# Integrators.net
KiCad netlist of a schematic drawn in Altium Designer
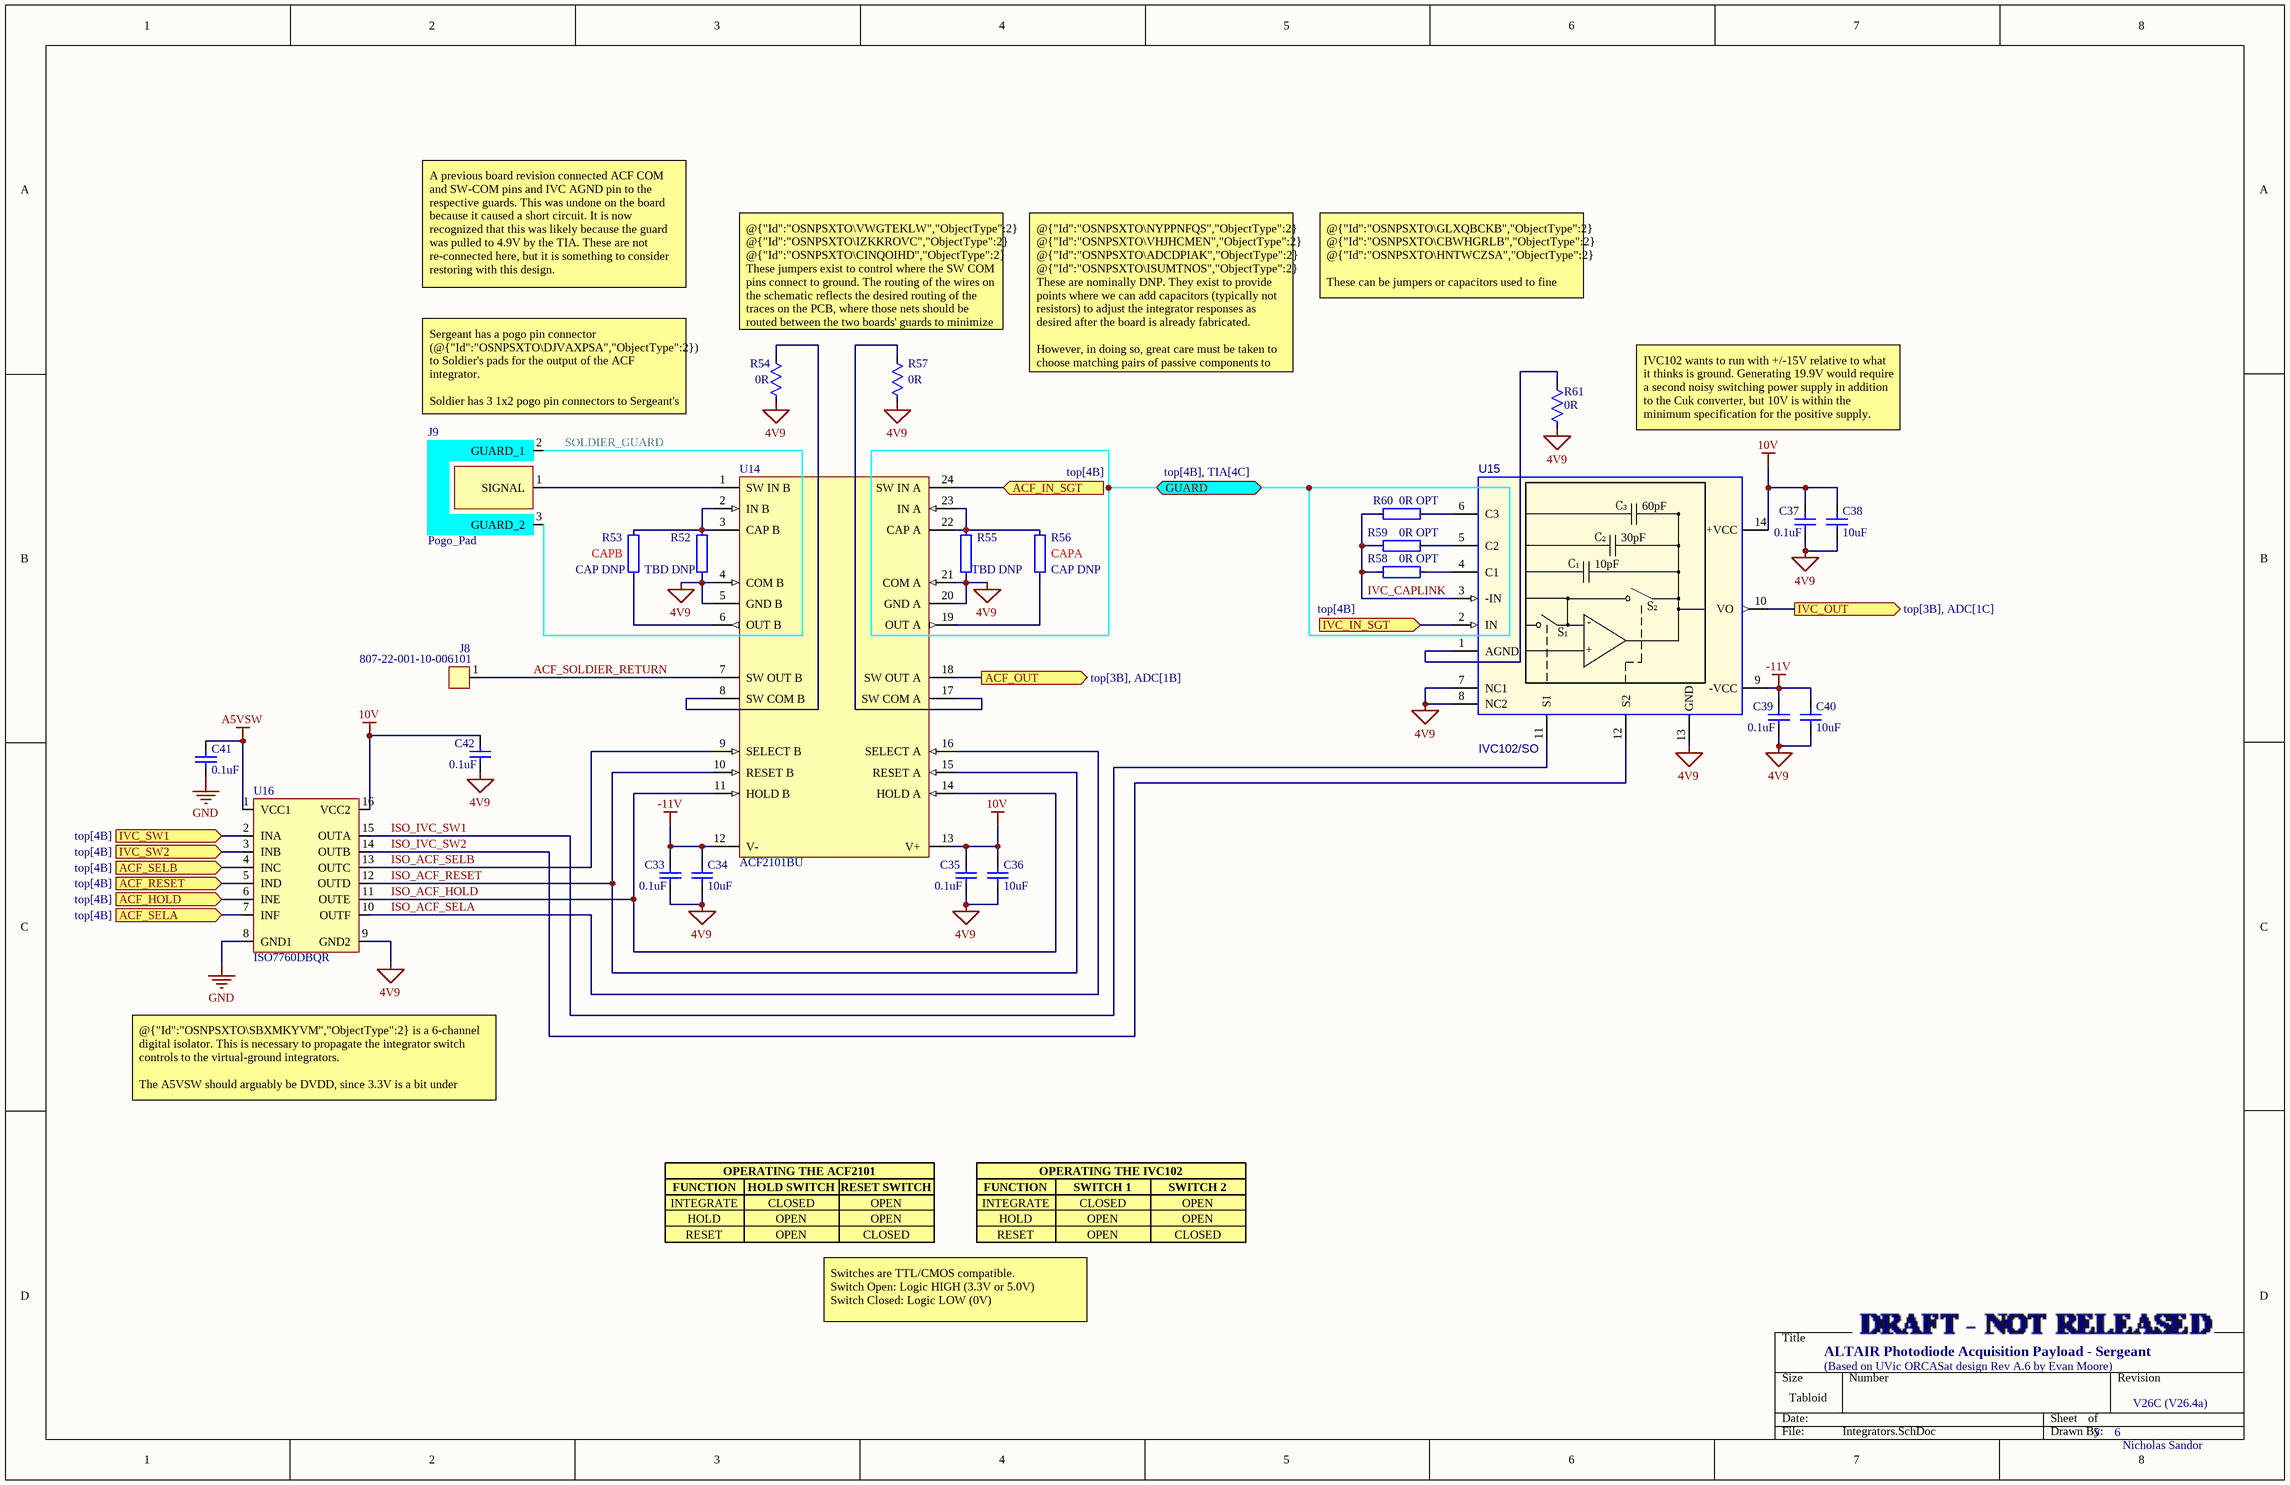
[diagram p0: Integrators.SchDoc]

(export (version "E")
  (design (tool "Eeschema 10.0.6"))
  (components
    (comp (ref "C33")
      (value "0.1uF")
      (footprint "CAP 0603 NON-IPC KEMET X7R")
      (description "Kemet C0603C104K5RACAUTO - Cap Ceramic 0.1uF 50V X7R 10% 0603 125C Paper T/R")
      (fields (field (name "MF") "Kemet") (field (name "MP") "C0603C104K5RACAUTO"))
      (libsource (lib "ALTAIR_PD_Capacitors") (part "CAP"))
    )
    (comp (ref "C34")
      (value "10uF")
      (footprint "CAP 0805 IPC MID DENSITY")
      (description "Murata GRM21BR61E106KA73L - Cap Ceramic 10uF 10% 25V X5R 0805")
      (fields (field (name "MF") "Murata") (field (name "MP") "GRM21BR61E106KA73L"))
      (libsource (lib "ALTAIR_PD_Capacitors") (part "CAP"))
    )
    (comp (ref "C35")
      (value "0.1uF")
      (footprint "CAP 0603 NON-IPC KEMET X7R")
      (description "Kemet C0603C104K5RACAUTO - Cap Ceramic 0.1uF 50V X7R 10% 0603 125C Paper T/R")
      (fields (field (name "MF") "Kemet") (field (name "MP") "C0603C104K5RACAUTO"))
      (libsource (lib "ALTAIR_PD_Capacitors") (part "CAP"))
    )
    (comp (ref "C36")
      (value "10uF")
      (footprint "CAP 0805 IPC MID DENSITY")
      (description "Murata GRM21BR61E106KA73L - Cap Ceramic 10uF 10% 25V X5R 0805")
      (fields (field (name "MF") "Murata") (field (name "MP") "GRM21BR61E106KA73L"))
      (libsource (lib "ALTAIR_PD_Capacitors") (part "CAP"))
    )
    (comp (ref "C37")
      (value "0.1uF")
      (footprint "CAP 0603 NON-IPC KEMET X7R")
      (description "Kemet C0603C104K5RACAUTO - Cap Ceramic 0.1uF 50V X7R 10% 0603 125C Paper T/R")
      (fields (field (name "MF") "Kemet") (field (name "MP") "C0603C104K5RACAUTO"))
      (libsource (lib "ALTAIR_PD_Capacitors") (part "CAP"))
    )
    (comp (ref "C38")
      (value "10uF")
      (footprint "CAP 0805 IPC MID DENSITY")
      (description "Murata GRM21BR61E106KA73L - Cap Ceramic 10uF 10% 25V X5R 0805")
      (fields (field (name "MF") "Murata") (field (name "MP") "GRM21BR61E106KA73L"))
      (libsource (lib "ALTAIR_PD_Capacitors") (part "CAP"))
    )
    (comp (ref "C39")
      (value "0.1uF")
      (footprint "CAP 0603 NON-IPC KEMET X7R")
      (description "Kemet C0603C104K5RACAUTO - Cap Ceramic 0.1uF 50V X7R 10% 0603 125C Paper T/R")
      (fields (field (name "MF") "Kemet") (field (name "MP") "C0603C104K5RACAUTO"))
      (libsource (lib "ALTAIR_PD_Capacitors") (part "CAP"))
    )
    (comp (ref "C40")
      (value "10uF")
      (footprint "CAP 0805 IPC MID DENSITY")
      (description "Murata GRM21BR61E106KA73L - Cap Ceramic 10uF 10% 25V X5R 0805")
      (fields (field (name "MF") "Murata") (field (name "MP") "GRM21BR61E106KA73L"))
      (libsource (lib "ALTAIR_PD_Capacitors") (part "CAP"))
    )
    (comp (ref "C41")
      (value "0.1uF")
      (footprint "CAP 0603 IPC MID DENSITY")
      (description "Kemet C0603C104K5RACAUTO - Cap Ceramic 0.1uF 50V X7R 10% 0603 125C Paper T/R")
      (fields (field (name "MF") "Kemet") (field (name "MP") "C0603C104K5RACAUTO"))
      (libsource (lib "ALTAIR_PD_Capacitors") (part "CAP"))
    )
    (comp (ref "C42")
      (value "0.1uF")
      (footprint "CAP 0603 IPC MID DENSITY")
      (description "Kemet C0603C104K5RACAUTO - Cap Ceramic 0.1uF 50V X7R 10% 0603 125C Paper T/R")
      (fields (field (name "MF") "Kemet") (field (name "MP") "C0603C104K5RACAUTO"))
      (libsource (lib "ALTAIR_PD_Capacitors") (part "CAP"))
    )
    (comp (ref "J8")
      (value "807-22-001-10-006101")
      (footprint "POGO PIN 807-22-001-10-006101")
      (description "Mill-Max Individual Insulated Pin 5.99mm Initial Height")
      (fields (field (name "MF") "Mill-Max"))
      (libsource (lib "ALTAIR_PD_Pogo") (part "807-22-001-10-006101"))
    )
    (comp (ref "J9")
      (value "Pogo_Pad")
      (footprint "POGO PAD SERGEANT")
      (description "Pad for Pogo Pins with Guard")
      (libsource (lib "ALTAIR_PD_Pogo") (part "Pogo_Pad"))
    )
    (comp (ref "R52")
      (value "TBD DNP")
      (footprint "RES 0402 IPC LOW DENSITY")
      (description "Yageo RC0402JR-070RL - Res 0 Ohms 1/16W SMD 0402")
      (fields (field (name "MF") "YAGEO") (field (name "MP") "RC0402JR-070RL"))
      (libsource (lib "ALTAIR_PD_Resistors") (part "IMPEDANCE"))
    )
    (comp (ref "R53")
      (value "CAP DNP")
      (footprint "RES 0402 IPC LOW DENSITY")
      (description "Yageo RC0402JR-070RL - Res 0 Ohms 1/16W SMD 0402")
      (fields (field (name "MF") "YAGEO") (field (name "MP") "RC0402JR-070RL"))
      (libsource (lib "ALTAIR_PD_Resistors") (part "IMPEDANCE"))
    )
    (comp (ref "R54")
      (value "0R")
      (footprint "RES 0402 IPC MID DENSITY")
      (description "Yageo RC0402JR-070RL - Res 0 Ohms 1/16W SMD 0402")
      (fields (field (name "MF") "YAGEO") (field (name "MP") "RC0402JR-070RL"))
      (libsource (lib "ALTAIR_PD_Resistors") (part "RES"))
    )
    (comp (ref "R55")
      (value "TBD DNP")
      (footprint "RES 0402 IPC LOW DENSITY")
      (description "Yageo RC0402JR-070RL - Res 0 Ohms 1/16W SMD 0402")
      (fields (field (name "MF") "YAGEO") (field (name "MP") "RC0402JR-070RL"))
      (libsource (lib "ALTAIR_PD_Resistors") (part "IMPEDANCE"))
    )
    (comp (ref "R56")
      (value "CAP DNP")
      (footprint "RES 0402 IPC LOW DENSITY")
      (description "Yageo RC0402JR-070RL - Res 0 Ohms 1/16W SMD 0402")
      (fields (field (name "MF") "YAGEO") (field (name "MP") "RC0402JR-070RL"))
      (libsource (lib "ALTAIR_PD_Resistors") (part "IMPEDANCE"))
    )
    (comp (ref "R57")
      (value "0R")
      (footprint "RES 0402 IPC MID DENSITY")
      (description "Yageo RC0402JR-070RL - Res 0 Ohms 1/16W SMD 0402")
      (fields (field (name "MF") "YAGEO") (field (name "MP") "RC0402JR-070RL"))
      (libsource (lib "ALTAIR_PD_Resistors") (part "RES"))
    )
    (comp (ref "R58")
      (value "0R OPT")
      (footprint "RES 0402 IPC LOW DENSITY")
      (description "Yageo RC0402JR-070RL - Res 0 Ohms 1/16W SMD 0402")
      (fields (field (name "MF") "YAGEO") (field (name "MP") "RC0402JR-070RL"))
      (libsource (lib "ALTAIR_PD_Resistors") (part "IMPEDANCE"))
    )
    (comp (ref "R59")
      (value "0R OPT")
      (footprint "RES 0402 IPC LOW DENSITY")
      (description "Yageo RC0402JR-070RL - Res 0 Ohms 1/16W SMD 0402")
      (fields (field (name "MF") "YAGEO") (field (name "MP") "RC0402JR-070RL"))
      (libsource (lib "ALTAIR_PD_Resistors") (part "IMPEDANCE"))
    )
    (comp (ref "R60")
      (value "0R OPT")
      (footprint "RES 0402 IPC LOW DENSITY")
      (description "Yageo RC0402JR-070RL - Res 0 Ohms 1/16W SMD 0402")
      (fields (field (name "MF") "YAGEO") (field (name "MP") "RC0402JR-070RL"))
      (libsource (lib "ALTAIR_PD_Resistors") (part "IMPEDANCE"))
    )
    (comp (ref "R61")
      (value "0R")
      (footprint "RES 0402 IPC MID DENSITY")
      (description "Yageo RC0402JR-070RL - Res 0 Ohms 1/16W SMD 0402")
      (fields (field (name "MF") "YAGEO") (field (name "MP") "RC0402JR-070RL"))
      (libsource (lib "ALTAIR_PD_Resistors") (part "RES"))
    )
    (comp (ref "U14")
      (value "ACF2101BU")
      (footprint "ALTAIR_PD_SOIC:24-SOIC 7.6MM WIDE LOW DENSITY")
      (fields (field (name "MF") "Texas Instruments"))
      (libsource (lib "ALTAIR_PD_Amplifiers") (part "ACF2101BU"))
    )
    (comp (ref "U15")
      (value "IVC102/SO")
      (footprint "14-SOIC 4MM WIDE LOW DENSITY")
      (description "Precision Switched Integrator Transimpedance Amplifier")
      (fields (field (name "MF") "Texas Instruments") (field (name "MP") "IVC102U"))
      (libsource (lib "ALTAIR_PD_Amplifiers") (part "IVC102/SO_5"))
    )
    (comp (ref "U16")
      (value "ISO7760DBQR")
      (footprint "16-SSOP 0.635MM PITCH 5.4MM WIDTH NON-IPC TI")
      (description "Digital Isolator 6-Channel 6/0 Inputs 16SSOP")
      (fields (field (name "MF") "Texas Instruments"))
      (libsource (lib "ALTAIR_PD_DigitalLogic") (part "ISO7760DBQR"))
    )
  )
  (nets
    (net (code "1") (name "-11V") (class "Default")
      (node (ref "C33") (pin "2") (pinfunction "2_2") (pintype "passive"))
      (node (ref "C34") (pin "2") (pinfunction "2_2") (pintype "passive"))
      (node (ref "C39") (pin "2") (pinfunction "2_2") (pintype "passive"))
      (node (ref "C40") (pin "2") (pinfunction "2_2") (pintype "passive"))
      (node (ref "U14") (pin "12") (pinfunction "V-_12") (pintype "power_in"))
      (node (ref "U15") (pin "9") (pinfunction "-VCC_9") (pintype "power_in"))
    )
    (net (code "2") (name "/ACF_HOLD") (class "Default")
      (node (ref "U16") (pin "6") (pinfunction "INE_6") (pintype "passive"))
    )
    (net (code "3") (name "/ACF_IN_SGT") (class "Default")
      (node (ref "U14") (pin "24") (pinfunction "SW_IN_A_24") (pintype "passive"))
    )
    (net (code "4") (name "/ACF_OUT") (class "Default")
      (node (ref "U14") (pin "18") (pinfunction "SW_OUT_A_18") (pintype "passive"))
    )
    (net (code "5") (name "/ACF_RESET") (class "Default")
      (node (ref "U16") (pin "5") (pinfunction "IND_5") (pintype "passive"))
    )
    (net (code "6") (name "/ACF_SELA") (class "Default")
      (node (ref "U16") (pin "7") (pinfunction "INF_7") (pintype "passive"))
    )
    (net (code "7") (name "/ACF_SELB") (class "Default")
      (node (ref "U16") (pin "4") (pinfunction "INC_4") (pintype "passive"))
    )
    (net (code "8") (name "/ACF_SOLDIER_RETURN") (class "Default")
      (node (ref "J8") (pin "1") (pinfunction "1_1") (pintype "passive"))
      (node (ref "U14") (pin "7") (pinfunction "SW_OUT_B_7") (pintype "passive"))
    )
    (net (code "10") (name "/ISO_ACF_HOLD") (class "Default")
      (node (ref "U14") (pin "11") (pinfunction "HOLD_B_11") (pintype "input"))
      (node (ref "U14") (pin "14") (pinfunction "HOLD_A_14") (pintype "input"))
      (node (ref "U16") (pin "11") (pinfunction "OUTE_11") (pintype "passive"))
    )
    (net (code "11") (name "/ISO_ACF_RESET") (class "Default")
      (node (ref "U14") (pin "10") (pinfunction "RESET_B_10") (pintype "input"))
      (node (ref "U14") (pin "15") (pinfunction "RESET_A_15") (pintype "input"))
      (node (ref "U16") (pin "12") (pinfunction "OUTD_12") (pintype "passive"))
    )
    (net (code "12") (name "/ISO_ACF_SELA") (class "Default")
      (node (ref "U14") (pin "16") (pinfunction "SELECT_A_16") (pintype "input"))
      (node (ref "U16") (pin "10") (pinfunction "OUTF_10") (pintype "passive"))
    )
    (net (code "13") (name "/ISO_ACF_SELB") (class "Default")
      (node (ref "U14") (pin "9") (pinfunction "SELECT_B_9") (pintype "input"))
      (node (ref "U16") (pin "13") (pinfunction "OUTC_13") (pintype "passive"))
    )
    (net (code "14") (name "/ISO_IVC_SW1") (class "Default")
      (node (ref "U15") (pin "11") (pinfunction "S1_11") (pintype "passive"))
      (node (ref "U16") (pin "15") (pinfunction "OUTA_15") (pintype "passive"))
    )
    (net (code "15") (name "/ISO_IVC_SW2") (class "Default")
      (node (ref "U15") (pin "12") (pinfunction "S2_12") (pintype "passive"))
      (node (ref "U16") (pin "14") (pinfunction "OUTB_14") (pintype "passive"))
    )
    (net (code "16") (name "/IVC_CAPLINK") (class "Default")
      (node (ref "R58") (pin "1") (pinfunction "1_1") (pintype "passive"))
      (node (ref "R59") (pin "1") (pinfunction "1_1") (pintype "passive"))
      (node (ref "R60") (pin "1") (pinfunction "1_1") (pintype "passive"))
      (node (ref "U15") (pin "3") (pinfunction "-IN_3") (pintype "input"))
    )
    (net (code "17") (name "/IVC_IN_SGT") (class "Default")
      (node (ref "U15") (pin "2") (pinfunction "IN_2") (pintype "input"))
    )
    (net (code "18") (name "/IVC_OUT") (class "Default")
      (node (ref "U15") (pin "10") (pinfunction "VO_10") (pintype "output"))
    )
    (net (code "19") (name "/IVC_SW1") (class "Default")
      (node (ref "U16") (pin "2") (pinfunction "INA_2") (pintype "passive"))
    )
    (net (code "20") (name "/IVC_SW2") (class "Default")
      (node (ref "U16") (pin "3") (pinfunction "INB_3") (pintype "passive"))
    )
    (net (code "21") (name "/SOLDIER_GUARD") (class "Default")
      (node (ref "J9") (pin "2") (pinfunction "GUARD_1_2") (pintype "passive"))
      (node (ref "J9") (pin "3") (pinfunction "GUARD_2_3") (pintype "passive"))
    )
    (net (code "22") (name "4V9") (class "Default")
      (node (ref "C33") (pin "1") (pinfunction "1_1") (pintype "passive"))
      (node (ref "C34") (pin "1") (pinfunction "1_1") (pintype "passive"))
      (node (ref "C35") (pin "1") (pinfunction "1_1") (pintype "passive"))
      (node (ref "C36") (pin "1") (pinfunction "1_1") (pintype "passive"))
      (node (ref "C37") (pin "1") (pinfunction "1_1") (pintype "passive"))
      (node (ref "C38") (pin "1") (pinfunction "1_1") (pintype "passive"))
      (node (ref "C39") (pin "1") (pinfunction "1_1") (pintype "passive"))
      (node (ref "C40") (pin "1") (pinfunction "1_1") (pintype "passive"))
      (node (ref "C42") (pin "1") (pinfunction "1_1") (pintype "passive"))
      (node (ref "R52") (pin "1") (pinfunction "1_1") (pintype "passive"))
      (node (ref "R54") (pin "2") (pinfunction "2_2") (pintype "passive"))
      (node (ref "R55") (pin "1") (pinfunction "1_1") (pintype "passive"))
      (node (ref "R57") (pin "2") (pinfunction "2_2") (pintype "passive"))
      (node (ref "R61") (pin "2") (pinfunction "2_2") (pintype "passive"))
      (node (ref "U14") (pin "20") (pinfunction "GND_A_20") (pintype "power_in"))
      (node (ref "U14") (pin "21") (pinfunction "COM_A_21") (pintype "input"))
      (node (ref "U14") (pin "4") (pinfunction "COM_B_4") (pintype "input"))
      (node (ref "U14") (pin "5") (pinfunction "GND_B_5") (pintype "power_in"))
      (node (ref "U15") (pin "13") (pinfunction "GND_13") (pintype "power_in"))
      (node (ref "U15") (pin "7") (pinfunction "NC1_7") (pintype "passive"))
      (node (ref "U15") (pin "8") (pinfunction "NC2_8") (pintype "passive"))
      (node (ref "U16") (pin "9") (pinfunction "GND2_9") (pintype "passive"))
    )
    (net (code "23") (name "10V") (class "Default")
      (node (ref "C35") (pin "2") (pinfunction "2_2") (pintype "passive"))
      (node (ref "C36") (pin "2") (pinfunction "2_2") (pintype "passive"))
      (node (ref "C37") (pin "2") (pinfunction "2_2") (pintype "passive"))
      (node (ref "C38") (pin "2") (pinfunction "2_2") (pintype "passive"))
      (node (ref "C42") (pin "2") (pinfunction "2_2") (pintype "passive"))
      (node (ref "U14") (pin "13") (pinfunction "V+_13") (pintype "power_in"))
      (node (ref "U15") (pin "14") (pinfunction "+VCC_14") (pintype "power_in"))
      (node (ref "U16") (pin "16") (pinfunction "VCC2_16") (pintype "passive"))
    )
    (net (code "24") (name "A5VSW") (class "Default")
      (node (ref "C41") (pin "2") (pinfunction "2_2") (pintype "passive"))
      (node (ref "U16") (pin "1") (pinfunction "VCC1_1") (pintype "passive"))
    )
    (net (code "25") (name "GND") (class "Default")
      (node (ref "C41") (pin "1") (pinfunction "1_1") (pintype "passive"))
      (node (ref "U16") (pin "8") (pinfunction "GND1_8") (pintype "passive"))
    )
    (net (code "26") (name "Net-(J9-SIGNAL)") (class "Default")
      (node (ref "J9") (pin "1") (pinfunction "SIGNAL_1") (pintype "passive"))
      (node (ref "U14") (pin "1") (pinfunction "SW_IN_B_1") (pintype "passive"))
    )
    (net (code "27") (name "Net-(U14-CAP_A)") (class "Default")
      (node (ref "R55") (pin "2") (pinfunction "2_2") (pintype "passive"))
      (node (ref "R56") (pin "2") (pinfunction "2_2") (pintype "passive"))
      (node (ref "U14") (pin "22") (pinfunction "CAP_A_22") (pintype "passive"))
      (node (ref "U14") (pin "23") (pinfunction "IN_A_23") (pintype "input"))
    )
    (net (code "28") (name "Net-(U14-CAP_B)") (class "Default")
      (node (ref "R52") (pin "2") (pinfunction "2_2") (pintype "passive"))
      (node (ref "R53") (pin "2") (pinfunction "2_2") (pintype "passive"))
      (node (ref "U14") (pin "2") (pinfunction "IN_B_2") (pintype "input"))
      (node (ref "U14") (pin "3") (pinfunction "CAP_B_3") (pintype "passive"))
    )
    (net (code "29") (name "Net-(U14-OUT_A)") (class "Default")
      (node (ref "R56") (pin "1") (pinfunction "1_1") (pintype "passive"))
      (node (ref "U14") (pin "19") (pinfunction "OUT_A_19") (pintype "output"))
    )
    (net (code "30") (name "Net-(U14-OUT_B)") (class "Default")
      (node (ref "R53") (pin "1") (pinfunction "1_1") (pintype "passive"))
      (node (ref "U14") (pin "6") (pinfunction "OUT_B_6") (pintype "output"))
    )
    (net (code "31") (name "Net-(U14-SW_COM_A)") (class "Default")
      (node (ref "R57") (pin "1") (pinfunction "1_1") (pintype "passive"))
      (node (ref "U14") (pin "17") (pinfunction "SW_COM_A_17") (pintype "passive"))
    )
    (net (code "32") (name "Net-(U14-SW_COM_B)") (class "Default")
      (node (ref "R54") (pin "1") (pinfunction "1_1") (pintype "passive"))
      (node (ref "U14") (pin "8") (pinfunction "SW_COM_B_8") (pintype "passive"))
    )
    (net (code "33") (name "Net-(U15-AGND)") (class "Default")
      (node (ref "R61") (pin "1") (pinfunction "1_1") (pintype "passive"))
      (node (ref "U15") (pin "1") (pinfunction "AGND_1") (pintype "power_in"))
    )
    (net (code "34") (name "Net-(U15-C1)") (class "Default")
      (node (ref "R58") (pin "2") (pinfunction "2_2") (pintype "passive"))
      (node (ref "U15") (pin "4") (pinfunction "C1_4") (pintype "passive"))
    )
    (net (code "35") (name "Net-(U15-C2)") (class "Default")
      (node (ref "R59") (pin "2") (pinfunction "2_2") (pintype "passive"))
      (node (ref "U15") (pin "5") (pinfunction "C2_5") (pintype "passive"))
    )
    (net (code "36") (name "Net-(U15-C3)") (class "Default")
      (node (ref "R60") (pin "2") (pinfunction "2_2") (pintype "passive"))
      (node (ref "U15") (pin "6") (pinfunction "C3_6") (pintype "passive"))
    )
  )
)
